# Debug.net
KiCad netlist of a schematic drawn in Altium Designer
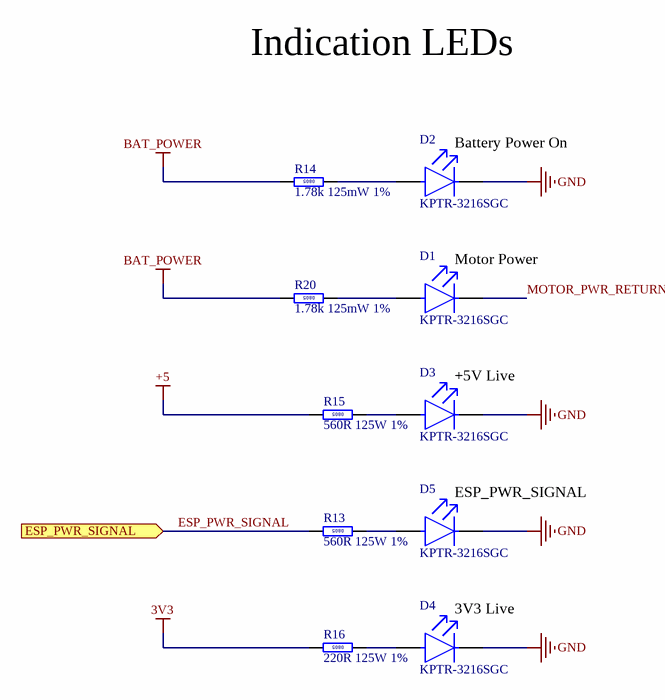
[diagram p0: Debug.SchDoc]

(export (version "E")
  (design (tool "Eeschema 10.0.6"))
  (components
    (comp (ref "D1")
      (value "KPTR-3216SGC")
      (footprint "KPTR-3216SGC-Footprint-1")
      (description "Single Color LED, Super Bright Green, Water Clear, 1.6mm")
      (fields (field (name "MANUFACTURER") "Kingbright"))
      (libsource (lib "Andor Technology") (part "KPTR-3216SGC-Symbol-1"))
    )
    (comp (ref "D2")
      (value "KPTR-3216SGC")
      (footprint "KPTR-3216SGC-Footprint-1")
      (description "Single Color LED, Super Bright Green, Water Clear, 1.6mm")
      (fields (field (name "MANUFACTURER") "Kingbright"))
      (libsource (lib "Andor Technology") (part "KPTR-3216SGC-Symbol-1"))
    )
    (comp (ref "D3")
      (value "KPTR-3216SGC")
      (footprint "KPTR-3216SGC-Footprint-1")
      (description "Single Color LED, Super Bright Green, Water Clear, 1.6mm")
      (fields (field (name "MANUFACTURER") "Kingbright"))
      (libsource (lib "Andor Technology") (part "KPTR-3216SGC-Symbol-1"))
    )
    (comp (ref "D4")
      (value "KPTR-3216SGC")
      (footprint "KPTR-3216SGC-Footprint-1")
      (description "Single Color LED, Super Bright Green, Water Clear, 1.6mm")
      (fields (field (name "MANUFACTURER") "Kingbright"))
      (libsource (lib "Andor Technology") (part "KPTR-3216SGC-Symbol-1"))
    )
    (comp (ref "D5")
      (value "KPTR-3216SGC")
      (footprint "KPTR-3216SGC-Footprint-1")
      (description "Single Color LED, Super Bright Green, Water Clear, 1.6mm")
      (fields (field (name "MANUFACTURER") "Kingbright"))
      (libsource (lib "Andor Technology") (part "KPTR-3216SGC-Symbol-1"))
    )
    (comp (ref "R13")
      (value "560R 125W 1%")
      (footprint "RESC2013X60X35LL10T20")
      (description "Res, SMD, 560R, 125mW, 1%, ±100ppm, 0805")
      (fields (field (name "TOLERANCE") "1%") (field (name "MANUFACTURER") "Panasonic"))
      (libsource (lib "Andor Technology") (part "Resistor_0805"))
    )
    (comp (ref "R14")
      (value "1.78k 125mW 1%")
      (footprint "RESC2013X60X35LL10T20")
      (description "Res, SMD, 1.78k, 125mW, 1%, ±100ppm, 0805")
      (fields
        (field (name "MANUFACTURER") "Panasonic")
        (field (name "MANUFACTURERPARTNUMBER") "ERJ-6ENF1781V")
      )
      (libsource (lib "Andor Technology") (part "Resistor_0805"))
    )
    (comp (ref "R15")
      (value "560R 125W 1%")
      (footprint "RESC2013X60X35LL10T20")
      (description "Res, SMD, 560R, 125mW, 1%, ±100ppm, 0805")
      (fields (field (name "TOLERANCE") "1%") (field (name "MANUFACTURER") "Panasonic"))
      (libsource (lib "Andor Technology") (part "Resistor_0805"))
    )
    (comp (ref "R16")
      (value "220R 125W 1%")
      (footprint "RESC2013X60X35LL10T20")
      (description "Res, SMD, 560R, 125mW, 1%, ±100ppm, 0805")
      (fields (field (name "TOLERANCE") "1%") (field (name "MANUFACTURER") "Panasonic"))
      (libsource (lib "Andor Technology") (part "Resistor_0805"))
    )
    (comp (ref "R20")
      (value "1.78k 125mW 1%")
      (footprint "RESC2013X60X35LL10T20")
      (description "Res, SMD, 1.78k, 125mW, 1%, ±100ppm, 0805")
      (fields
        (field (name "MANUFACTURER") "Panasonic")
        (field (name "MANUFACTURERPARTNUMBER") "ERJ-6ENF1781V")
      )
      (libsource (lib "Andor Technology") (part "Resistor_0805"))
    )
  )
  (nets
    (net (code "1") (name "+5") (class "Default")
      (node (ref "R15") (pin "2") (pinfunction "2_2") (pintype "passive"))
    )
    (net (code "2") (name "/ESP_PWR_SIGNAL") (class "Default")
      (node (ref "R13") (pin "2") (pinfunction "2_2") (pintype "passive"))
    )
    (net (code "3") (name "/MOTOR_PWR_RETURN") (class "Default")
      (node (ref "D1") (pin "2") (pinfunction "C_2") (pintype "passive"))
    )
    (net (code "4") (name "3V3") (class "Default")
      (node (ref "R16") (pin "2") (pinfunction "2_2") (pintype "passive"))
    )
    (net (code "5") (name "BAT_POWER") (class "Default")
      (node (ref "R14") (pin "2") (pinfunction "2_2") (pintype "passive"))
      (node (ref "R20") (pin "2") (pinfunction "2_2") (pintype "passive"))
    )
    (net (code "6") (name "GND") (class "Default")
      (node (ref "D2") (pin "2") (pinfunction "C_2") (pintype "passive"))
      (node (ref "D3") (pin "2") (pinfunction "C_2") (pintype "passive"))
      (node (ref "D4") (pin "2") (pinfunction "C_2") (pintype "passive"))
      (node (ref "D5") (pin "2") (pinfunction "C_2") (pintype "passive"))
    )
    (net (code "7") (name "Net-(D1-A)") (class "Default")
      (node (ref "D1") (pin "1") (pinfunction "A_1") (pintype "passive"))
      (node (ref "R20") (pin "1") (pinfunction "1_1") (pintype "passive"))
    )
    (net (code "8") (name "Net-(D2-A)") (class "Default")
      (node (ref "D2") (pin "1") (pinfunction "A_1") (pintype "passive"))
      (node (ref "R14") (pin "1") (pinfunction "1_1") (pintype "passive"))
    )
    (net (code "9") (name "Net-(D3-A)") (class "Default")
      (node (ref "D3") (pin "1") (pinfunction "A_1") (pintype "passive"))
      (node (ref "R15") (pin "1") (pinfunction "1_1") (pintype "passive"))
    )
    (net (code "10") (name "Net-(D4-A)") (class "Default")
      (node (ref "D4") (pin "1") (pinfunction "A_1") (pintype "passive"))
      (node (ref "R16") (pin "1") (pinfunction "1_1") (pintype "passive"))
    )
    (net (code "11") (name "Net-(D5-A)") (class "Default")
      (node (ref "D5") (pin "1") (pinfunction "A_1") (pintype "passive"))
      (node (ref "R13") (pin "1") (pinfunction "1_1") (pintype "passive"))
    )
  )
)
